# OOBD-Cup_v6.net
KiCad netlist of a schematic drawn in EAGLE
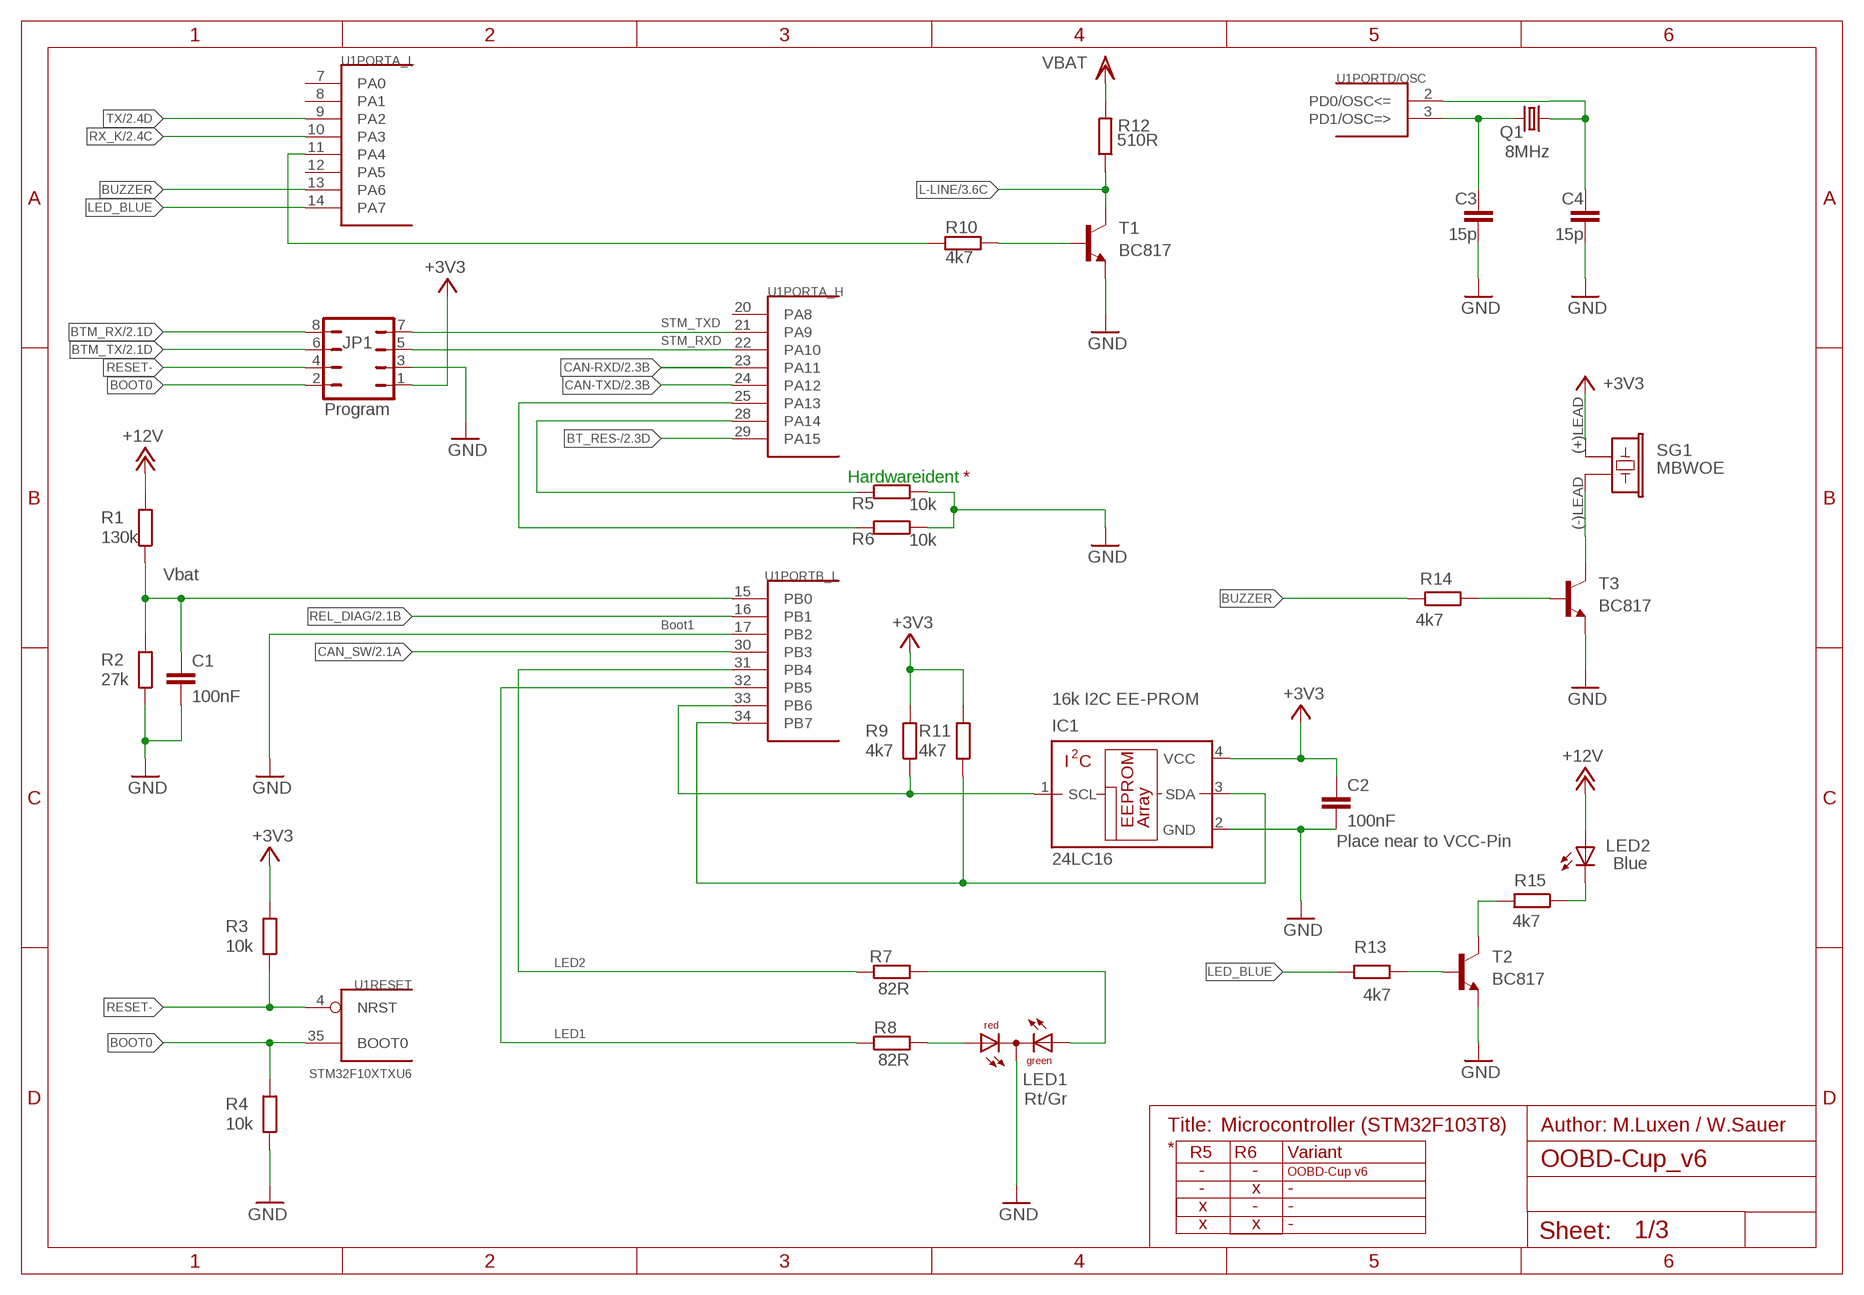
[diagram p0: schematic, sheet 1]
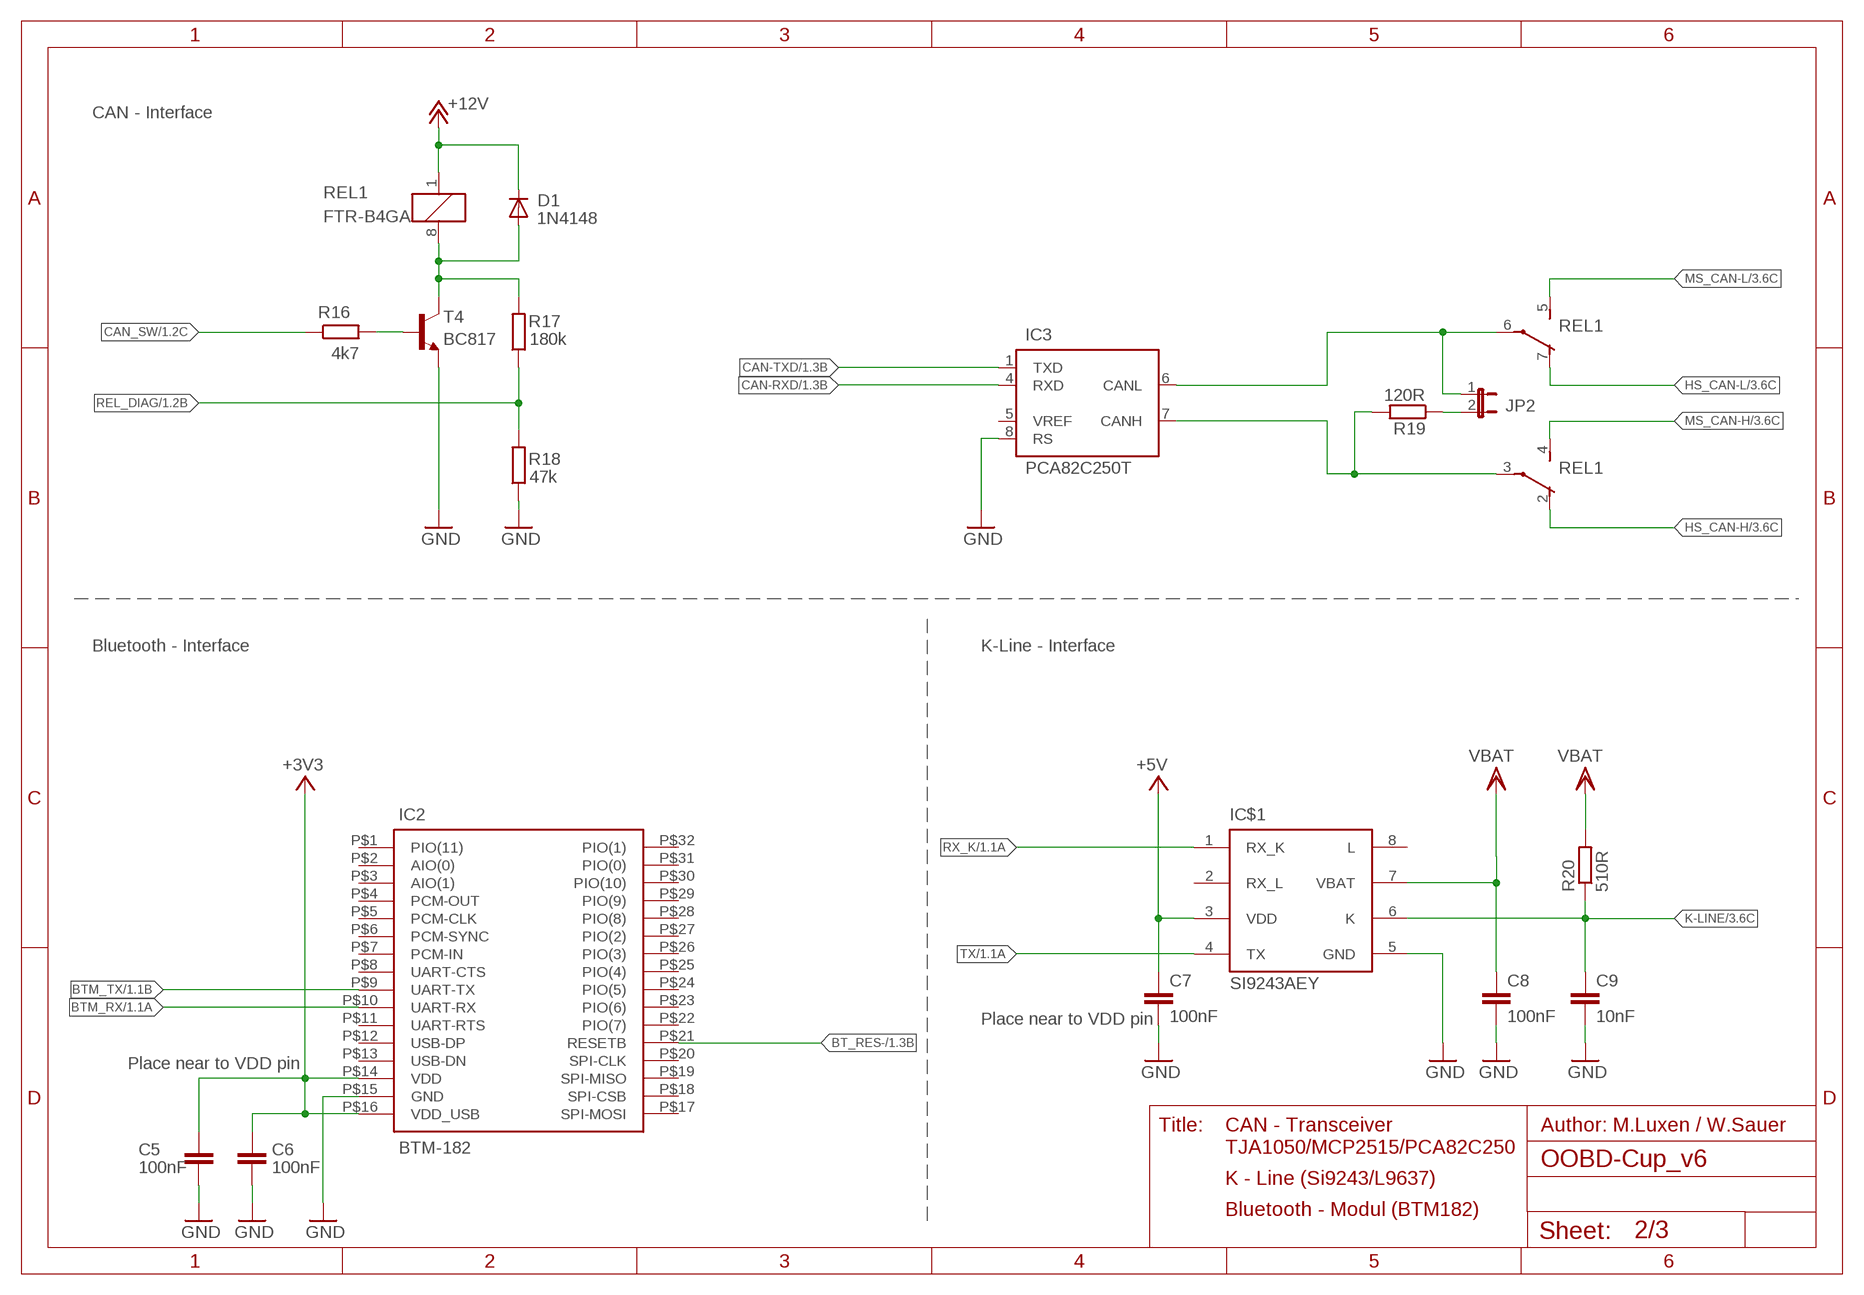
[diagram p1: schematic, sheet 2]
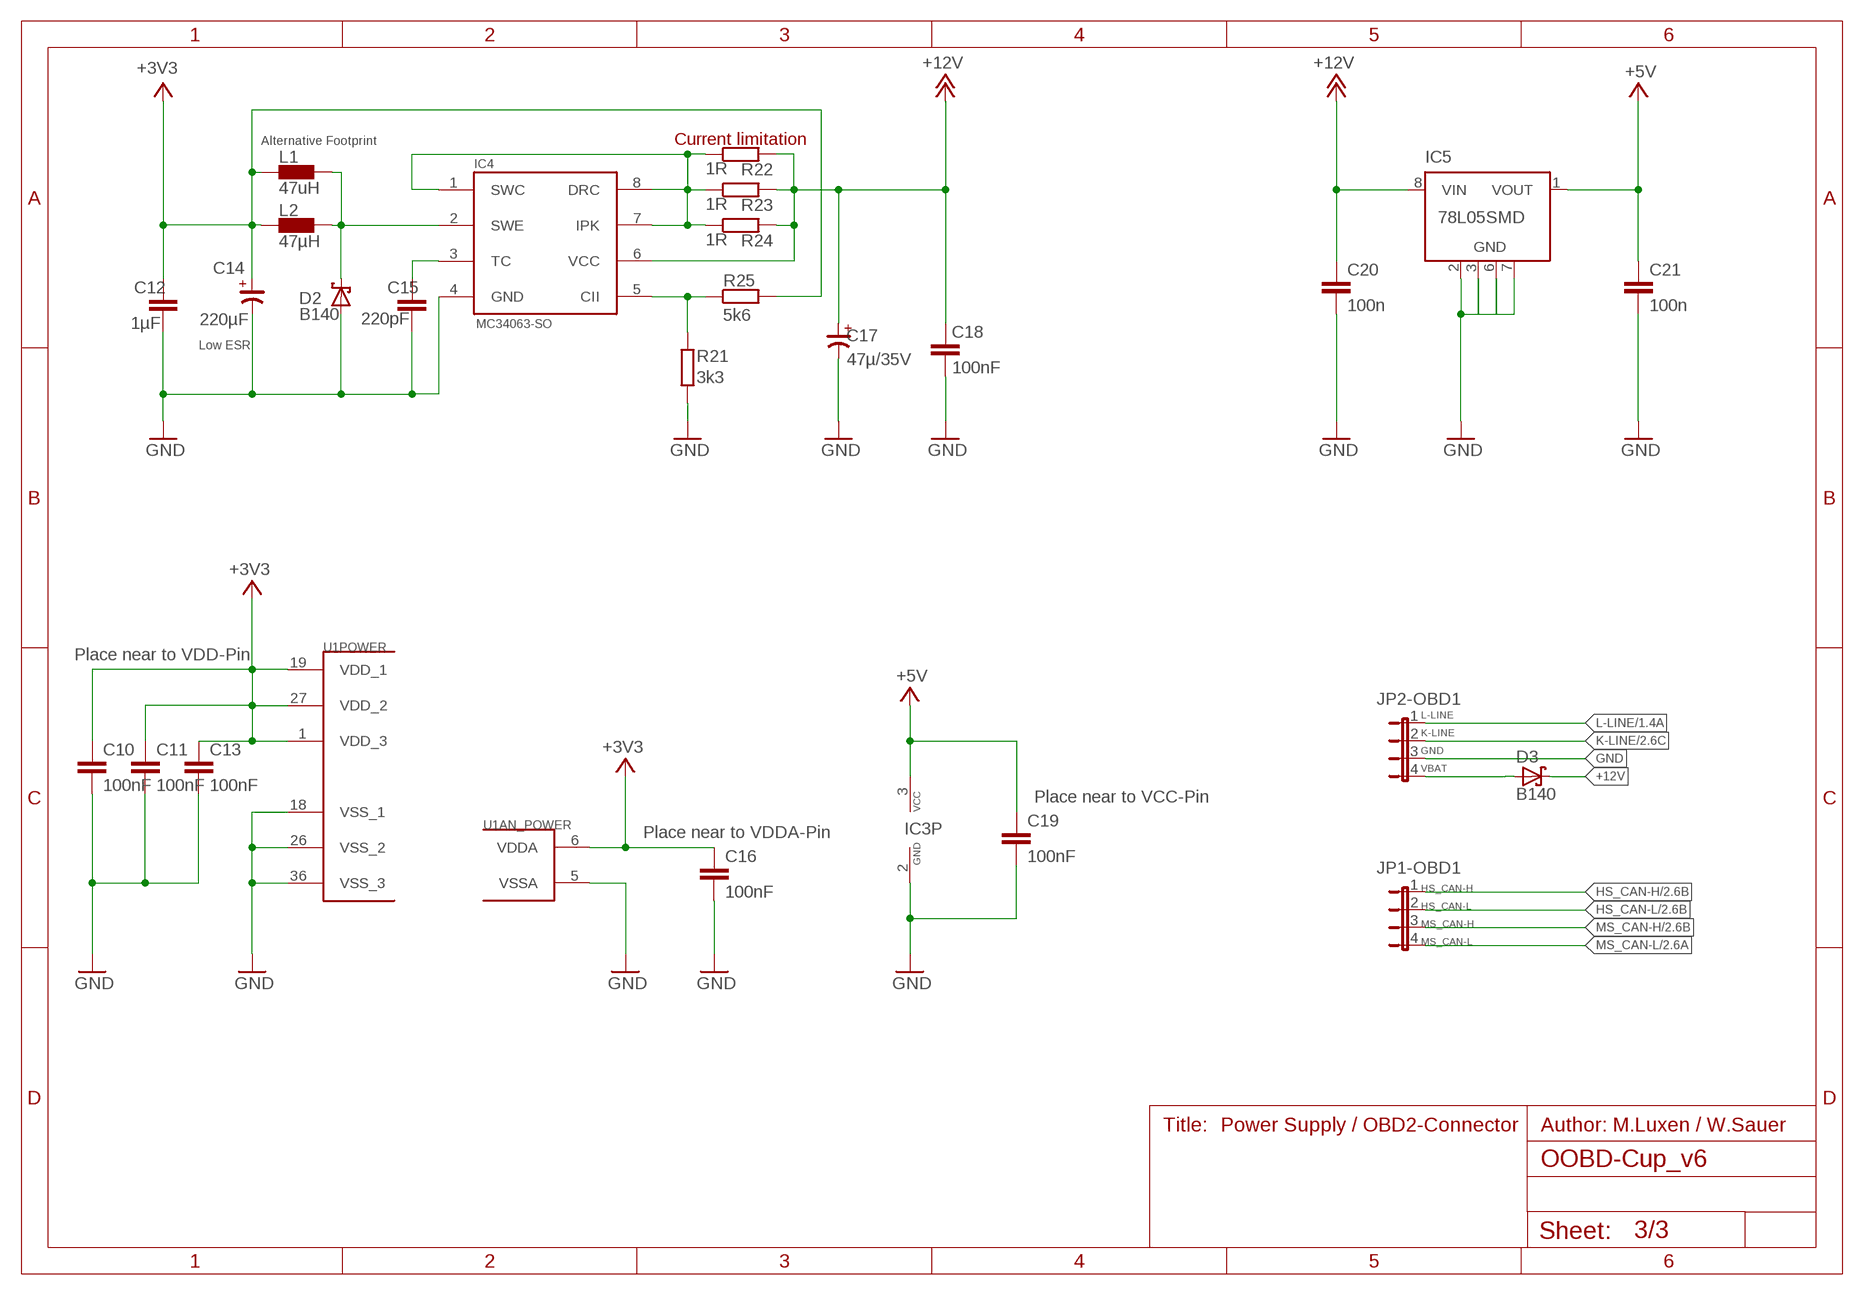
[diagram p2: schematic, sheet 3]

(export (version "E")
  (design (tool "Eeschema 10.0.6"))
  (components
    (comp (ref "C1")
      (value "100nF")
      (footprint "eagle-import:C0603")
      (libsource (lib "eagle-import") (part "resistor_C-EUC0603"))
    )
    (comp (ref "C2")
      (value "100nF")
      (footprint "eagle-import:C0603")
      (libsource (lib "eagle-import") (part "C-EUC0603"))
    )
    (comp (ref "C3")
      (value "15p")
      (footprint "eagle-import:C0603")
      (libsource (lib "eagle-import") (part "resistor_C-EUC0603"))
    )
    (comp (ref "C4")
      (value "15p")
      (footprint "eagle-import:C0603")
      (libsource (lib "eagle-import") (part "resistor_C-EUC0603"))
    )
    (comp (ref "IC1")
      (value "24LC16")
      (footprint "eagle-import:SOT23-5L")
      (fields (field (name "MF") "MICROCHIP") (field (name "MPN") "24LC00T-I/OT"))
      (libsource (lib "eagle-import") (part "2400OTLC"))
    )
    (comp (ref "JP1")
      (value "Program")
      (footprint "eagle-import:JP4Q")
      (libsource (lib "eagle-import") (part "JP4Q"))
    )
    (comp (ref "LED1")
      (value "Rt/Gr")
      (footprint "eagle-import:DUOLED2X5")
      (libsource (lib "eagle-import") (part "DUOLED2X5"))
    )
    (comp (ref "LED2")
      (value "Blue")
      (footprint "eagle-import:U57X32")
      (libsource (lib "eagle-import") (part "LEDSQR5.7X3.2"))
    )
    (comp (ref "Q1")
      (value "8MHz")
      (footprint "eagle-import:CTS406")
      (libsource (lib "eagle-import") (part "CRYSTALCTS406"))
    )
    (comp (ref "R1")
      (value "130k")
      (footprint "eagle-import:R0603")
      (libsource (lib "eagle-import") (part "resistor_R-EU_R0603"))
    )
    (comp (ref "R2")
      (value "27k")
      (footprint "eagle-import:R0603")
      (libsource (lib "eagle-import") (part "resistor_R-EU_R0603"))
    )
    (comp (ref "R3")
      (value "10k")
      (footprint "eagle-import:R0603")
      (libsource (lib "eagle-import") (part "resistor_R-EU_R0603"))
    )
    (comp (ref "R4")
      (value "10k")
      (footprint "eagle-import:R0603")
      (libsource (lib "eagle-import") (part "resistor_R-EU_R0603"))
    )
    (comp (ref "R5")
      (value "10k")
      (footprint "eagle-import:R0603")
      (libsource (lib "eagle-import") (part "R-EU_R0603"))
    )
    (comp (ref "R6")
      (value "10k")
      (footprint "eagle-import:R0603")
      (libsource (lib "eagle-import") (part "R-EU_R0603"))
    )
    (comp (ref "R7")
      (value "82R")
      (footprint "eagle-import:R0603")
      (libsource (lib "eagle-import") (part "R-EU_R0603"))
    )
    (comp (ref "R8")
      (value "82R")
      (footprint "eagle-import:R0603")
      (libsource (lib "eagle-import") (part "R-EU_R0603"))
    )
    (comp (ref "R9")
      (value "4k7")
      (footprint "eagle-import:R0603")
      (libsource (lib "eagle-import") (part "resistor_R-EU_R0603"))
    )
    (comp (ref "R10")
      (value "4k7")
      (footprint "eagle-import:R0603")
      (libsource (lib "eagle-import") (part "R-EU_R0603"))
    )
    (comp (ref "R11")
      (value "4k7")
      (footprint "eagle-import:R0603")
      (libsource (lib "eagle-import") (part "resistor_R-EU_R0603"))
    )
    (comp (ref "R12")
      (value "510R")
      (footprint "eagle-import:R0603")
      (libsource (lib "eagle-import") (part "R-EU_R0603"))
    )
    (comp (ref "R13")
      (value "4k7")
      (footprint "eagle-import:R0603")
      (libsource (lib "eagle-import") (part "R-EU_R0603"))
    )
    (comp (ref "R14")
      (value "4k7")
      (footprint "eagle-import:R0603")
      (libsource (lib "eagle-import") (part "R-EU_R0603"))
    )
    (comp (ref "R15")
      (value "4k7")
      (footprint "eagle-import:R0603")
      (libsource (lib "eagle-import") (part "R-EU_R0603"))
    )
    (comp (ref "SG1")
      (value "MBWOE")
      (footprint "eagle-import:BME0603SA")
      (fields (field (name "MF") "Grewus"))
      (libsource (lib "eagle-import") (part "MBWOE"))
    )
    (comp (ref "T1")
      (value "BC817")
      (footprint "eagle-import:SOT23")
      (libsource (lib "eagle-import") (part "BC847"))
    )
    (comp (ref "T2")
      (value "BC817")
      (footprint "eagle-import:SOT23")
      (libsource (lib "eagle-import") (part "BC847"))
    )
    (comp (ref "T3")
      (value "BC817")
      (footprint "eagle-import:SOT23")
      (libsource (lib "eagle-import") (part "BC847"))
    )
    (comp (ref "U1")
      (value "STM32F10XTXU6")
      (footprint "eagle-import:VFQFPN36")
      (libsource (lib "eagle-import") (part "STM32F10XTXU6"))
    )
    (comp (ref "C10")
      (value "100nF")
      (footprint "eagle-import:C0603")
      (libsource (lib "eagle-import") (part "resistor_C-EUC0603"))
    )
    (comp (ref "C11")
      (value "100nF")
      (footprint "eagle-import:C0603")
      (libsource (lib "eagle-import") (part "resistor_C-EUC0603"))
    )
    (comp (ref "C12")
      (value "1µF")
      (footprint "eagle-import:C0603K")
      (libsource (lib "eagle-import") (part "C-EUC0603K"))
    )
    (comp (ref "C13")
      (value "100nF")
      (footprint "eagle-import:C0603")
      (libsource (lib "eagle-import") (part "resistor_C-EUC0603"))
    )
    (comp (ref "C14")
      (value "220µF")
      (footprint "eagle-import:C6032-TE-C")
      (libsource (lib "eagle-import") (part "CP_6032-TE-C"))
    )
    (comp (ref "C15")
      (value "220pF")
      (footprint "eagle-import:C0603K")
      (libsource (lib "eagle-import") (part "C-EUC0603K"))
    )
    (comp (ref "C16")
      (value "100nF")
      (footprint "eagle-import:C0603")
      (libsource (lib "eagle-import") (part "resistor_C-EUC0603"))
    )
    (comp (ref "C17")
      (value "47µ/35V")
      (footprint "eagle-import:SV-D")
      (libsource (lib "eagle-import") (part "CP-SV-D"))
    )
    (comp (ref "C18")
      (value "100nF")
      (footprint "eagle-import:C0603K")
      (libsource (lib "eagle-import") (part "C-EUC0603K"))
    )
    (comp (ref "C19")
      (value "100nF")
      (footprint "eagle-import:C0603")
      (libsource (lib "eagle-import") (part "resistor_C-EUC0603"))
    )
    (comp (ref "C20")
      (value "100n")
      (footprint "eagle-import:C0603")
      (libsource (lib "eagle-import") (part "resistor_C-EUC0603"))
    )
    (comp (ref "C21")
      (value "100n")
      (footprint "eagle-import:C0603")
      (libsource (lib "eagle-import") (part "resistor_C-EUC0603"))
    )
    (comp (ref "D2")
      (value "B140")
      (footprint "eagle-import:SMB")
      (libsource (lib "eagle-import") (part "SCHOTTKY-DIODESMD"))
    )
    (comp (ref "D3")
      (value "B140")
      (footprint "eagle-import:SMB")
      (libsource (lib "eagle-import") (part "SCHOTTKY-DIODESMD"))
    )
    (comp (ref "IC3")
      (value "PCA82C250T")
      (footprint "eagle-import:SO08")
      (libsource (lib "eagle-import") (part "PCA82C250T"))
    )
    (comp (ref "IC4")
      (value "MC34063-SO")
      (footprint "eagle-import:SO8")
      (libsource (lib "eagle-import") (part "MC34063-SO"))
    )
    (comp (ref "IC5")
      (value "78L05SMD")
      (footprint "eagle-import:SO08")
      (libsource (lib "eagle-import") (part "78LSMD05"))
    )
    (comp (ref "JP1-OBD1")
      (value "JP4E")
      (footprint "eagle-import:JP4")
      (libsource (lib "eagle-import") (part "JP4E"))
    )
    (comp (ref "JP2-OBD1")
      (value "JP4E")
      (footprint "eagle-import:JP4")
      (libsource (lib "eagle-import") (part "JP4E"))
    )
    (comp (ref "L1")
      (value "47uH")
      (footprint "eagle-import:PIS2408")
      (libsource (lib "eagle-import") (part "PIS2408"))
    )
    (comp (ref "L2")
      (value "47µH")
      (footprint "eagle-import:07HCP-XXXX-50")
      (libsource (lib "eagle-import") (part "07HCP-XXXX-50"))
    )
    (comp (ref "R21")
      (value "3k3")
      (footprint "eagle-import:R0603")
      (libsource (lib "eagle-import") (part "R-EU_R0603"))
    )
    (comp (ref "R22")
      (value "1R")
      (footprint "eagle-import:R0805")
      (libsource (lib "eagle-import") (part "R-EU_R0805"))
    )
    (comp (ref "R23")
      (value "1R")
      (footprint "eagle-import:R0805")
      (libsource (lib "eagle-import") (part "R-EU_R0805"))
    )
    (comp (ref "R24")
      (value "1R")
      (footprint "eagle-import:R0805")
      (libsource (lib "eagle-import") (part "R-EU_R0805"))
    )
    (comp (ref "R25")
      (value "5k6")
      (footprint "eagle-import:R0603")
      (libsource (lib "eagle-import") (part "R-EU_R0603"))
    )
    (comp (ref "C5")
      (value "100nF")
      (footprint "eagle-import:C0603")
      (libsource (lib "eagle-import") (part "C-EUC0603"))
    )
    (comp (ref "C6")
      (value "100nF")
      (footprint "eagle-import:C0603")
      (libsource (lib "eagle-import") (part "C-EUC0603"))
    )
    (comp (ref "C7")
      (value "100nF")
      (footprint "eagle-import:C0603")
      (libsource (lib "eagle-import") (part "resistor_C-EUC0603"))
    )
    (comp (ref "C8")
      (value "100nF")
      (footprint "eagle-import:C0603")
      (libsource (lib "eagle-import") (part "resistor_C-EUC0603"))
    )
    (comp (ref "C9")
      (value "10nF")
      (footprint "eagle-import:C0603")
      (libsource (lib "eagle-import") (part "resistor_C-EUC0603"))
    )
    (comp (ref "D1")
      (value "1N4148")
      (footprint "eagle-import:MINIMELF")
      (libsource (lib "eagle-import") (part "DIODE-MINIMELF"))
    )
    (comp (ref "IC$1")
      (value "SI9243AEY")
      (footprint "eagle-import:SO08")
      (libsource (lib "eagle-import") (part "SI9243AEY"))
    )
    (comp (ref "IC2")
      (value "BTM-182")
      (footprint "eagle-import:BTM-182")
      (libsource (lib "eagle-import") (part "BTM-182"))
    )
    (comp (ref "JP2")
      (value "JP1E")
      (footprint "eagle-import:JP1")
      (libsource (lib "eagle-import") (part "JP1E"))
    )
    (comp (ref "R16")
      (value "4k7")
      (footprint "eagle-import:R0603")
      (libsource (lib "eagle-import") (part "R-EU_R0603"))
    )
    (comp (ref "R17")
      (value "180k")
      (footprint "eagle-import:R0603")
      (libsource (lib "eagle-import") (part "R-EU_R0603"))
    )
    (comp (ref "R18")
      (value "47k")
      (footprint "eagle-import:R0603")
      (libsource (lib "eagle-import") (part "R-EU_R0603"))
    )
    (comp (ref "R19")
      (value "120R")
      (footprint "eagle-import:R0603")
      (libsource (lib "eagle-import") (part "resistor_R-EU_R0603"))
    )
    (comp (ref "R20")
      (value "510R")
      (footprint "eagle-import:R0603")
      (libsource (lib "eagle-import") (part "resistor_R-EU_R0603"))
    )
    (comp (ref "REL1")
      (value "FTR-B4GA")
      (footprint "eagle-import:FTR-B4GA")
      (fields (field (name "MPN") "FTR-B4GAxxxZ"))
      (libsource (lib "eagle-import") (part "FTR-B4GA"))
    )
    (comp (ref "T4")
      (value "BC817")
      (footprint "eagle-import:SOT23")
      (libsource (lib "eagle-import") (part "BC847"))
    )
  )
  (nets
    (net (code "1") (name "+3V3") (class "Default")
      (node (ref "C10") (pin "1") (pinfunction "1_1") (pintype "passive"))
      (node (ref "C11") (pin "1") (pinfunction "1_1") (pintype "passive"))
      (node (ref "C12") (pin "1") (pinfunction "1_1") (pintype "passive"))
      (node (ref "C13") (pin "1") (pinfunction "1_1") (pintype "passive"))
      (node (ref "C14") (pin "+") (pinfunction "+_+") (pintype "passive"))
      (node (ref "C16") (pin "1") (pinfunction "1_1") (pintype "passive"))
      (node (ref "C2") (pin "1") (pinfunction "1_1") (pintype "passive"))
      (node (ref "C5") (pin "1") (pinfunction "1_1") (pintype "passive"))
      (node (ref "C6") (pin "1") (pinfunction "1_1") (pintype "passive"))
      (node (ref "IC1") (pin "4") (pinfunction "VCC_4") (pintype "power_in"))
      (node (ref "IC2") (pin "P$14") (pinfunction "VDD_P$14") (pintype "power_in"))
      (node (ref "IC2") (pin "P$16") (pinfunction "VDD_USB_P$16") (pintype "power_in"))
      (node (ref "JP1") (pin "1") (pinfunction "1_1") (pintype "passive"))
      (node (ref "L1") (pin "P$1") (pinfunction "P$1_P$1") (pintype "bidirectional"))
      (node (ref "L2") (pin "1") (pinfunction "P$1_1") (pintype "bidirectional"))
      (node (ref "R11") (pin "2") (pinfunction "2_2") (pintype "passive"))
      (node (ref "R25") (pin "2") (pinfunction "2_2") (pintype "passive"))
      (node (ref "R3") (pin "2") (pinfunction "2_2") (pintype "passive"))
      (node (ref "R9") (pin "2") (pinfunction "2_2") (pintype "passive"))
      (node (ref "SG1") (pin "(+)LEAD") (pinfunction "1_(+)LEAD") (pintype "passive"))
      (node (ref "U1") (pin "1") (pinfunction "VDD_3_1") (pintype "power_in"))
      (node (ref "U1") (pin "19") (pinfunction "VDD_1_19") (pintype "power_in"))
      (node (ref "U1") (pin "27") (pinfunction "VDD_2_27") (pintype "power_in"))
      (node (ref "U1") (pin "6") (pinfunction "VDDA_6") (pintype "power_in"))
    )
    (net (code "2") (name "+5V") (class "Default")
      (node (ref "C19") (pin "1") (pinfunction "1_1") (pintype "passive"))
      (node (ref "C21") (pin "1") (pinfunction "1_1") (pintype "passive"))
      (node (ref "C7") (pin "1") (pinfunction "1_1") (pintype "passive"))
      (node (ref "IC$1") (pin "3") (pinfunction "VDD_3") (pintype "bidirectional"))
      (node (ref "IC3") (pin "3") (pinfunction "VCC_3") (pintype "power_in"))
      (node (ref "IC5") (pin "1") (pinfunction "VOUT_1") (pintype "output"))
    )
    (net (code "3") (name "+12V") (class "Default")
      (node (ref "C17") (pin "+") (pinfunction "+_+") (pintype "passive"))
      (node (ref "C18") (pin "1") (pinfunction "1_1") (pintype "passive"))
      (node (ref "C20") (pin "1") (pinfunction "1_1") (pintype "passive"))
      (node (ref "D1") (pin "C") (pinfunction "C_C") (pintype "passive"))
      (node (ref "D3") (pin "C") (pinfunction "C_C") (pintype "passive"))
      (node (ref "IC4") (pin "6") (pinfunction "VCC_6") (pintype "bidirectional"))
      (node (ref "IC5") (pin "8") (pinfunction "VIN_8") (pintype "passive"))
      (node (ref "LED2") (pin "A") (pinfunction "A_A") (pintype "passive"))
      (node (ref "R1") (pin "2") (pinfunction "2_2") (pintype "passive"))
      (node (ref "R22") (pin "2") (pinfunction "2_2") (pintype "passive"))
      (node (ref "R23") (pin "2") (pinfunction "2_2") (pintype "passive"))
      (node (ref "R24") (pin "2") (pinfunction "2_2") (pintype "passive"))
      (node (ref "REL1") (pin "1") (pinfunction "1_1") (pintype "passive"))
    )
    (net (code "4") (name "BOOT0") (class "Default")
      (node (ref "JP1") (pin "2") (pinfunction "2_2") (pintype "passive"))
      (node (ref "R4") (pin "2") (pinfunction "2_2") (pintype "passive"))
      (node (ref "U1") (pin "35") (pinfunction "BOOT0_35") (pintype "input"))
    )
    (net (code "5") (name "BTM_RX") (class "Default")
      (node (ref "IC2") (pin "P$10") (pinfunction "UART-RX_P$10") (pintype "input"))
      (node (ref "JP1") (pin "8") (pinfunction "8_8") (pintype "passive"))
    )
    (net (code "6") (name "BTM_TX") (class "Default")
      (node (ref "IC2") (pin "P$9") (pinfunction "UART-TX_P$9") (pintype "output"))
      (node (ref "JP1") (pin "6") (pinfunction "6_6") (pintype "passive"))
    )
    (net (code "7") (name "BT_RES-") (class "Default")
      (node (ref "IC2") (pin "P$21") (pinfunction "RESETB_P$21") (pintype "input"))
      (node (ref "U1") (pin "29") (pinfunction "PA15_29") (pintype "bidirectional"))
    )
    (net (code "8") (name "BUZZER") (class "Default")
      (node (ref "R14") (pin "1") (pinfunction "1_1") (pintype "passive"))
      (node (ref "U1") (pin "13") (pinfunction "PA6_13") (pintype "bidirectional"))
    )
    (net (code "9") (name "CAN-RXD") (class "Default")
      (node (ref "IC3") (pin "4") (pinfunction "RXD_4") (pintype "bidirectional"))
      (node (ref "U1") (pin "23") (pinfunction "PA11_23") (pintype "bidirectional"))
    )
    (net (code "10") (name "CAN-TXD") (class "Default")
      (node (ref "IC3") (pin "1") (pinfunction "TXD_1") (pintype "bidirectional"))
      (node (ref "U1") (pin "24") (pinfunction "PA12_24") (pintype "bidirectional"))
    )
    (net (code "11") (name "CAN_SW") (class "Default")
      (node (ref "R16") (pin "1") (pinfunction "1_1") (pintype "passive"))
      (node (ref "U1") (pin "30") (pinfunction "PB3_30") (pintype "bidirectional"))
    )
    (net (code "12") (name "GND") (class "Default")
      (node (ref "C1") (pin "2") (pinfunction "2_2") (pintype "passive"))
      (node (ref "C10") (pin "2") (pinfunction "2_2") (pintype "passive"))
      (node (ref "C11") (pin "2") (pinfunction "2_2") (pintype "passive"))
      (node (ref "C12") (pin "2") (pinfunction "2_2") (pintype "passive"))
      (node (ref "C13") (pin "2") (pinfunction "2_2") (pintype "passive"))
      (node (ref "C14") (pin "-") (pinfunction "-_-") (pintype "passive"))
      (node (ref "C15") (pin "2") (pinfunction "2_2") (pintype "passive"))
      (node (ref "C16") (pin "2") (pinfunction "2_2") (pintype "passive"))
      (node (ref "C17") (pin "-") (pinfunction "-_-") (pintype "passive"))
      (node (ref "C18") (pin "2") (pinfunction "2_2") (pintype "passive"))
      (node (ref "C19") (pin "2") (pinfunction "2_2") (pintype "passive"))
      (node (ref "C2") (pin "2") (pinfunction "2_2") (pintype "passive"))
      (node (ref "C20") (pin "2") (pinfunction "2_2") (pintype "passive"))
      (node (ref "C21") (pin "2") (pinfunction "2_2") (pintype "passive"))
      (node (ref "C3") (pin "1") (pinfunction "1_1") (pintype "passive"))
      (node (ref "C4") (pin "1") (pinfunction "1_1") (pintype "passive"))
      (node (ref "C5") (pin "2") (pinfunction "2_2") (pintype "passive"))
      (node (ref "C6") (pin "2") (pinfunction "2_2") (pintype "passive"))
      (node (ref "C7") (pin "2") (pinfunction "2_2") (pintype "passive"))
      (node (ref "C8") (pin "2") (pinfunction "2_2") (pintype "passive"))
      (node (ref "C9") (pin "2") (pinfunction "2_2") (pintype "passive"))
      (node (ref "D2") (pin "A") (pinfunction "A_A") (pintype "passive"))
      (node (ref "IC$1") (pin "5") (pinfunction "GND_5") (pintype "bidirectional"))
      (node (ref "IC1") (pin "2") (pinfunction "GND_2") (pintype "power_in"))
      (node (ref "IC2") (pin "P$15") (pinfunction "GND_P$15") (pintype "power_in"))
      (node (ref "IC3") (pin "2") (pinfunction "GND_2") (pintype "power_in"))
      (node (ref "IC3") (pin "8") (pinfunction "RS_8") (pintype "bidirectional"))
      (node (ref "IC4") (pin "4") (pinfunction "GND_4") (pintype "power_in"))
      (node (ref "IC5") (pin "2") (pinfunction "GND_2") (pintype "power_in"))
      (node (ref "IC5") (pin "3") (pinfunction "GND_3") (pintype "power_in"))
      (node (ref "IC5") (pin "6") (pinfunction "GND_6") (pintype "power_in"))
      (node (ref "IC5") (pin "7") (pinfunction "GND_7") (pintype "power_in"))
      (node (ref "JP1") (pin "3") (pinfunction "3_3") (pintype "passive"))
      (node (ref "JP2-OBD1") (pin "3") (pinfunction "3_3") (pintype "passive"))
      (node (ref "LED1") (pin "K") (pinfunction "C_K") (pintype "passive"))
      (node (ref "R18") (pin "1") (pinfunction "1_1") (pintype "passive"))
      (node (ref "R2") (pin "1") (pinfunction "1_1") (pintype "passive"))
      (node (ref "R21") (pin "2") (pinfunction "2_2") (pintype "passive"))
      (node (ref "R4") (pin "1") (pinfunction "1_1") (pintype "passive"))
      (node (ref "R5") (pin "2") (pinfunction "2_2") (pintype "passive"))
      (node (ref "R6") (pin "2") (pinfunction "2_2") (pintype "passive"))
      (node (ref "T1") (pin "2") (pinfunction "E_2") (pintype "passive"))
      (node (ref "T2") (pin "2") (pinfunction "E_2") (pintype "passive"))
      (node (ref "T3") (pin "2") (pinfunction "E_2") (pintype "passive"))
      (node (ref "T4") (pin "2") (pinfunction "E_2") (pintype "passive"))
      (node (ref "U1") (pin "17") (pinfunction "PB2_17") (pintype "bidirectional"))
      (node (ref "U1") (pin "18") (pinfunction "VSS_1_18") (pintype "power_in"))
      (node (ref "U1") (pin "26") (pinfunction "VSS_2_26") (pintype "power_in"))
      (node (ref "U1") (pin "36") (pinfunction "VSS_3_36") (pintype "power_in"))
      (node (ref "U1") (pin "5") (pinfunction "VSSA_5") (pintype "power_in"))
    )
    (net (code "13") (name "HS_CAN-H") (class "Default")
      (node (ref "JP1-OBD1") (pin "1") (pinfunction "1_1") (pintype "passive"))
      (node (ref "REL1") (pin "2") (pinfunction "O_2") (pintype "passive"))
    )
    (net (code "14") (name "HS_CAN-L") (class "Default")
      (node (ref "JP1-OBD1") (pin "2") (pinfunction "2_2") (pintype "passive"))
      (node (ref "REL1") (pin "7") (pinfunction "O_7") (pintype "passive"))
    )
    (net (code "15") (name "K-LINE") (class "Default")
      (node (ref "C9") (pin "1") (pinfunction "1_1") (pintype "passive"))
      (node (ref "IC$1") (pin "6") (pinfunction "K_6") (pintype "bidirectional"))
      (node (ref "JP2-OBD1") (pin "2") (pinfunction "2_2") (pintype "passive"))
      (node (ref "R20") (pin "1") (pinfunction "1_1") (pintype "passive"))
    )
    (net (code "16") (name "L-LINE") (class "Default")
      (node (ref "JP2-OBD1") (pin "1") (pinfunction "1_1") (pintype "passive"))
      (node (ref "R12") (pin "1") (pinfunction "1_1") (pintype "passive"))
      (node (ref "T1") (pin "3") (pinfunction "C_3") (pintype "passive"))
    )
    (net (code "17") (name "LED1") (class "Default")
      (node (ref "R8") (pin "1") (pinfunction "1_1") (pintype "passive"))
      (node (ref "U1") (pin "32") (pinfunction "PB5_32") (pintype "bidirectional"))
    )
    (net (code "18") (name "LED2") (class "Default")
      (node (ref "R7") (pin "1") (pinfunction "1_1") (pintype "passive"))
      (node (ref "U1") (pin "31") (pinfunction "PB4_31") (pintype "bidirectional"))
    )
    (net (code "19") (name "LED_BLUE") (class "Default")
      (node (ref "R13") (pin "1") (pinfunction "1_1") (pintype "passive"))
      (node (ref "U1") (pin "14") (pinfunction "PA7_14") (pintype "bidirectional"))
    )
    (net (code "20") (name "MS_CAN-H") (class "Default")
      (node (ref "JP1-OBD1") (pin "3") (pinfunction "3_3") (pintype "passive"))
      (node (ref "REL1") (pin "4") (pinfunction "S_4") (pintype "passive"))
    )
    (net (code "21") (name "MS_CAN-L") (class "Default")
      (node (ref "JP1-OBD1") (pin "4") (pinfunction "4_4") (pintype "passive"))
      (node (ref "REL1") (pin "5") (pinfunction "S_5") (pintype "passive"))
    )
    (net (code "22") (name "Net-(IC1-SCL)") (class "Default")
      (node (ref "IC1") (pin "1") (pinfunction "SCL_1") (pintype "input"))
      (node (ref "R9") (pin "1") (pinfunction "1_1") (pintype "passive"))
      (node (ref "U1") (pin "33") (pinfunction "PB6_33") (pintype "bidirectional"))
    )
    (net (code "23") (name "Net-(IC1-SDA)") (class "Default")
      (node (ref "IC1") (pin "3") (pinfunction "SDA_3") (pintype "bidirectional"))
      (node (ref "R11") (pin "1") (pinfunction "1_1") (pintype "passive"))
      (node (ref "U1") (pin "34") (pinfunction "PB7_34") (pintype "bidirectional"))
    )
    (net (code "24") (name "Net-(IC3A-CANH)") (class "Default")
      (node (ref "IC3") (pin "7") (pinfunction "CANH_7") (pintype "bidirectional"))
      (node (ref "R19") (pin "2") (pinfunction "2_2") (pintype "passive"))
      (node (ref "REL1") (pin "3") (pinfunction "P_3") (pintype "passive"))
    )
    (net (code "25") (name "Net-(IC3A-CANL)") (class "Default")
      (node (ref "IC3") (pin "6") (pinfunction "CANL_6") (pintype "bidirectional"))
      (node (ref "JP2") (pin "1") (pinfunction "1_1") (pintype "passive"))
      (node (ref "REL1") (pin "6") (pinfunction "P_6") (pintype "passive"))
    )
    (net (code "26") (name "Net-(IC4-CII)") (class "Default")
      (node (ref "IC4") (pin "5") (pinfunction "CII_5") (pintype "bidirectional"))
      (node (ref "R21") (pin "1") (pinfunction "1_1") (pintype "passive"))
      (node (ref "R25") (pin "1") (pinfunction "1_1") (pintype "passive"))
    )
    (net (code "27") (name "Net-(IC4-DRC)") (class "Default")
      (node (ref "IC4") (pin "1") (pinfunction "SWC_1") (pintype "bidirectional"))
      (node (ref "IC4") (pin "7") (pinfunction "IPK_7") (pintype "bidirectional"))
      (node (ref "IC4") (pin "8") (pinfunction "DRC_8") (pintype "bidirectional"))
      (node (ref "R22") (pin "1") (pinfunction "1_1") (pintype "passive"))
      (node (ref "R23") (pin "1") (pinfunction "1_1") (pintype "passive"))
      (node (ref "R24") (pin "1") (pinfunction "1_1") (pintype "passive"))
    )
    (net (code "28") (name "Net-(IC4-SWE)") (class "Default")
      (node (ref "D2") (pin "C") (pinfunction "C_C") (pintype "passive"))
      (node (ref "IC4") (pin "2") (pinfunction "SWE_2") (pintype "bidirectional"))
      (node (ref "L1") (pin "P$2") (pinfunction "P$2_P$2") (pintype "bidirectional"))
      (node (ref "L2") (pin "2") (pinfunction "P$2_2") (pintype "bidirectional"))
    )
    (net (code "29") (name "Net-(IC4-TC)") (class "Default")
      (node (ref "C15") (pin "1") (pinfunction "1_1") (pintype "passive"))
      (node (ref "IC4") (pin "3") (pinfunction "TC_3") (pintype "bidirectional"))
    )
    (net (code "30") (name "Net-(JP2-Pad2)") (class "Default")
      (node (ref "JP2") (pin "2") (pinfunction "2_2") (pintype "passive"))
      (node (ref "R19") (pin "1") (pinfunction "1_1") (pintype "passive"))
    )
    (net (code "31") (name "Net-(LED1-PadAG)") (class "Default")
      (node (ref "LED1") (pin "AG") (pinfunction "AG_AG") (pintype "passive"))
      (node (ref "R7") (pin "2") (pinfunction "2_2") (pintype "passive"))
    )
    (net (code "32") (name "Net-(LED1-PadAR)") (class "Default")
      (node (ref "LED1") (pin "AR") (pinfunction "AR_AR") (pintype "passive"))
      (node (ref "R8") (pin "2") (pinfunction "2_2") (pintype "passive"))
    )
    (net (code "33") (name "Net-(LED2-C)") (class "Default")
      (node (ref "LED2") (pin "K") (pinfunction "C_K") (pintype "passive"))
      (node (ref "R15") (pin "1") (pinfunction "1_1") (pintype "passive"))
    )
    (net (code "34") (name "Net-(Q1-2)") (class "Default")
      (node (ref "C3") (pin "2") (pinfunction "2_2") (pintype "passive"))
      (node (ref "Q1") (pin "3") (pinfunction "2_3") (pintype "passive"))
      (node (ref "U1") (pin "3") (pinfunction "PD1/OSC=>_3") (pintype "bidirectional"))
    )
    (net (code "35") (name "Net-(REL1A-2)") (class "Default")
      (node (ref "D1") (pin "A") (pinfunction "A_A") (pintype "passive"))
      (node (ref "R17") (pin "2") (pinfunction "2_2") (pintype "passive"))
      (node (ref "REL1") (pin "8") (pinfunction "2_8") (pintype "passive"))
      (node (ref "T4") (pin "3") (pinfunction "C_3") (pintype "passive"))
    )
    (net (code "36") (name "Net-(SG1-2)") (class "Default")
      (node (ref "SG1") (pin "(-)LEAD") (pinfunction "2_(-)LEAD") (pintype "passive"))
      (node (ref "T3") (pin "3") (pinfunction "C_3") (pintype "passive"))
    )
    (net (code "37") (name "Net-(T1-B)") (class "Default")
      (node (ref "R10") (pin "2") (pinfunction "2_2") (pintype "passive"))
      (node (ref "T1") (pin "1") (pinfunction "B_1") (pintype "passive"))
    )
    (net (code "38") (name "Net-(T2-B)") (class "Default")
      (node (ref "R13") (pin "2") (pinfunction "2_2") (pintype "passive"))
      (node (ref "T2") (pin "1") (pinfunction "B_1") (pintype "passive"))
    )
    (net (code "39") (name "Net-(T2-C)") (class "Default")
      (node (ref "R15") (pin "2") (pinfunction "2_2") (pintype "passive"))
      (node (ref "T2") (pin "3") (pinfunction "C_3") (pintype "passive"))
    )
    (net (code "40") (name "Net-(T3-B)") (class "Default")
      (node (ref "R14") (pin "2") (pinfunction "2_2") (pintype "passive"))
      (node (ref "T3") (pin "1") (pinfunction "B_1") (pintype "passive"))
    )
    (net (code "41") (name "Net-(T4-B)") (class "Default")
      (node (ref "R16") (pin "2") (pinfunction "2_2") (pintype "passive"))
      (node (ref "T4") (pin "1") (pinfunction "B_1") (pintype "passive"))
    )
    (net (code "42") (name "Net-(U1B-PA13)") (class "Default")
      (node (ref "R6") (pin "1") (pinfunction "1_1") (pintype "passive"))
      (node (ref "U1") (pin "25") (pinfunction "PA13_25") (pintype "bidirectional"))
    )
    (net (code "43") (name "Net-(U1B-PA14)") (class "Default")
      (node (ref "R5") (pin "1") (pinfunction "1_1") (pintype "passive"))
      (node (ref "U1") (pin "28") (pinfunction "PA14_28") (pintype "bidirectional"))
    )
    (net (code "44") (name "Net-(U1C-PA4)") (class "Default")
      (node (ref "R10") (pin "1") (pinfunction "1_1") (pintype "passive"))
      (node (ref "U1") (pin "11") (pinfunction "PA4_11") (pintype "bidirectional"))
    )
    (net (code "45") (name "Net-(U1D-PB0)") (class "Default")
      (node (ref "C1") (pin "1") (pinfunction "1_1") (pintype "passive"))
      (node (ref "R1") (pin "1") (pinfunction "1_1") (pintype "passive"))
      (node (ref "R2") (pin "2") (pinfunction "2_2") (pintype "passive"))
      (node (ref "U1") (pin "15") (pinfunction "PB0_15") (pintype "bidirectional"))
    )
    (net (code "46") (name "Net-(U1E-PD0{slash}OSC<=)") (class "Default")
      (node (ref "C4") (pin "2") (pinfunction "2_2") (pintype "passive"))
      (node (ref "Q1") (pin "1") (pinfunction "1_1") (pintype "passive"))
      (node (ref "U1") (pin "2") (pinfunction "PD0/OSC<=_2") (pintype "bidirectional"))
    )
    (net (code "47") (name "REL_DIAG") (class "Default")
      (node (ref "R17") (pin "1") (pinfunction "1_1") (pintype "passive"))
      (node (ref "R18") (pin "2") (pinfunction "2_2") (pintype "passive"))
      (node (ref "U1") (pin "16") (pinfunction "PB1_16") (pintype "bidirectional"))
    )
    (net (code "48") (name "RESET-") (class "Default")
      (node (ref "JP1") (pin "4") (pinfunction "4_4") (pintype "passive"))
      (node (ref "R3") (pin "1") (pinfunction "1_1") (pintype "passive"))
      (node (ref "U1") (pin "4") (pinfunction "NRST_4") (pintype "input"))
    )
    (net (code "49") (name "RX_K") (class "Default")
      (node (ref "IC$1") (pin "1") (pinfunction "RX_K_1") (pintype "bidirectional"))
      (node (ref "U1") (pin "10") (pinfunction "PA3_10") (pintype "bidirectional"))
    )
    (net (code "50") (name "STM_RXD") (class "Default")
      (node (ref "JP1") (pin "5") (pinfunction "5_5") (pintype "passive"))
      (node (ref "U1") (pin "22") (pinfunction "PA10_22") (pintype "bidirectional"))
    )
    (net (code "51") (name "STM_TXD") (class "Default")
      (node (ref "JP1") (pin "7") (pinfunction "7_7") (pintype "passive"))
      (node (ref "U1") (pin "21") (pinfunction "PA9_21") (pintype "bidirectional"))
    )
    (net (code "52") (name "TX") (class "Default")
      (node (ref "IC$1") (pin "4") (pinfunction "TX_4") (pintype "bidirectional"))
      (node (ref "U1") (pin "9") (pinfunction "PA2_9") (pintype "bidirectional"))
    )
    (net (code "53") (name "VBAT") (class "Default")
      (node (ref "C8") (pin "1") (pinfunction "1_1") (pintype "passive"))
      (node (ref "D3") (pin "A") (pinfunction "A_A") (pintype "passive"))
      (node (ref "IC$1") (pin "7") (pinfunction "VBAT_7") (pintype "bidirectional"))
      (node (ref "JP2-OBD1") (pin "4") (pinfunction "4_4") (pintype "passive"))
      (node (ref "R12") (pin "2") (pinfunction "2_2") (pintype "passive"))
      (node (ref "R20") (pin "2") (pinfunction "2_2") (pintype "passive"))
    )
    (net (code "54") (name "unconnected-(IC$1-L-Pad8)") (class "Default")
      (node (ref "IC$1") (pin "8") (pinfunction "L_8") (pintype "bidirectional"))
    )
    (net (code "55") (name "unconnected-(IC$1-RX_L-Pad2)") (class "Default")
      (node (ref "IC$1") (pin "2") (pinfunction "RX_L_2") (pintype "bidirectional"))
    )
    (net (code "56") (name "unconnected-(IC2-AIO(0)-PadP$2)") (class "Default")
      (node (ref "IC2") (pin "P$2") (pinfunction "AIO(0)_P$2") (pintype "bidirectional"))
    )
    (net (code "57") (name "unconnected-(IC2-AIO(1)-PadP$3)") (class "Default")
      (node (ref "IC2") (pin "P$3") (pinfunction "AIO(1)_P$3") (pintype "bidirectional"))
    )
    (net (code "58") (name "unconnected-(IC2-PCM-CLK-PadP$5)") (class "Default")
      (node (ref "IC2") (pin "P$5") (pinfunction "PCM-CLK_P$5") (pintype "bidirectional"))
    )
    (net (code "59") (name "unconnected-(IC2-PCM-IN-PadP$7)") (class "Default")
      (node (ref "IC2") (pin "P$7") (pinfunction "PCM-IN_P$7") (pintype "input"))
    )
    (net (code "60") (name "unconnected-(IC2-PCM-OUT-PadP$4)") (class "Default")
      (node (ref "IC2") (pin "P$4") (pinfunction "PCM-OUT_P$4") (pintype "output"))
    )
    (net (code "61") (name "unconnected-(IC2-PCM-SYNC-PadP$6)") (class "Default")
      (node (ref "IC2") (pin "P$6") (pinfunction "PCM-SYNC_P$6") (pintype "bidirectional"))
    )
    (net (code "62") (name "unconnected-(IC2-PIO(0)-PadP$31)") (class "Default")
      (node (ref "IC2") (pin "P$31") (pinfunction "PIO(0)_P$31") (pintype "bidirectional"))
    )
    (net (code "63") (name "unconnected-(IC2-PIO(1)-PadP$32)") (class "Default")
      (node (ref "IC2") (pin "P$32") (pinfunction "PIO(1)_P$32") (pintype "bidirectional"))
    )
    (net (code "64") (name "unconnected-(IC2-PIO(2)-PadP$27)") (class "Default")
      (node (ref "IC2") (pin "P$27") (pinfunction "PIO(2)_P$27") (pintype "bidirectional"))
    )
    (net (code "65") (name "unconnected-(IC2-PIO(3)-PadP$26)") (class "Default")
      (node (ref "IC2") (pin "P$26") (pinfunction "PIO(3)_P$26") (pintype "bidirectional"))
    )
    (net (code "66") (name "unconnected-(IC2-PIO(4)-PadP$25)") (class "Default")
      (node (ref "IC2") (pin "P$25") (pinfunction "PIO(4)_P$25") (pintype "bidirectional"))
    )
    (net (code "67") (name "unconnected-(IC2-PIO(5)-PadP$24)") (class "Default")
      (node (ref "IC2") (pin "P$24") (pinfunction "PIO(5)_P$24") (pintype "bidirectional"))
    )
    (net (code "68") (name "unconnected-(IC2-PIO(6)-PadP$23)") (class "Default")
      (node (ref "IC2") (pin "P$23") (pinfunction "PIO(6)_P$23") (pintype "bidirectional"))
    )
    (net (code "69") (name "unconnected-(IC2-PIO(7)-PadP$22)") (class "Default")
      (node (ref "IC2") (pin "P$22") (pinfunction "PIO(7)_P$22") (pintype "bidirectional"))
    )
    (net (code "70") (name "unconnected-(IC2-PIO(8)-PadP$28)") (class "Default")
      (node (ref "IC2") (pin "P$28") (pinfunction "PIO(8)_P$28") (pintype "bidirectional"))
    )
    (net (code "71") (name "unconnected-(IC2-PIO(9)-PadP$29)") (class "Default")
      (node (ref "IC2") (pin "P$29") (pinfunction "PIO(9)_P$29") (pintype "bidirectional"))
    )
    (net (code "72") (name "unconnected-(IC2-PIO(10)-PadP$30)") (class "Default")
      (node (ref "IC2") (pin "P$30") (pinfunction "PIO(10)_P$30") (pintype "bidirectional"))
    )
    (net (code "73") (name "unconnected-(IC2-PIO(11)-PadP$1)") (class "Default")
      (node (ref "IC2") (pin "P$1") (pinfunction "PIO(11)_P$1") (pintype "bidirectional"))
    )
    (net (code "74") (name "unconnected-(IC2-SPI-CLK-PadP$20)") (class "Default")
      (node (ref "IC2") (pin "P$20") (pinfunction "SPI-CLK_P$20") (pintype "input"))
    )
    (net (code "75") (name "unconnected-(IC2-SPI-CSB-PadP$18)") (class "Default")
      (node (ref "IC2") (pin "P$18") (pinfunction "SPI-CSB_P$18") (pintype "input"))
    )
    (net (code "76") (name "unconnected-(IC2-SPI-MISO-PadP$19)") (class "Default")
      (node (ref "IC2") (pin "P$19") (pinfunction "SPI-MISO_P$19") (pintype "output"))
    )
    (net (code "77") (name "unconnected-(IC2-SPI-MOSI-PadP$17)") (class "Default")
      (node (ref "IC2") (pin "P$17") (pinfunction "SPI-MOSI_P$17") (pintype "input"))
    )
    (net (code "78") (name "unconnected-(IC2-UART-CTS-PadP$8)") (class "Default")
      (node (ref "IC2") (pin "P$8") (pinfunction "UART-CTS_P$8") (pintype "input"))
    )
    (net (code "79") (name "unconnected-(IC2-UART-RTS-PadP$11)") (class "Default")
      (node (ref "IC2") (pin "P$11") (pinfunction "UART-RTS_P$11") (pintype "output"))
    )
    (net (code "80") (name "unconnected-(IC2-USB-DN-PadP$13)") (class "Default")
      (node (ref "IC2") (pin "P$13") (pinfunction "USB-DN_P$13") (pintype "bidirectional"))
    )
    (net (code "81") (name "unconnected-(IC2-USB-DP-PadP$12)") (class "Default")
      (node (ref "IC2") (pin "P$12") (pinfunction "USB-DP_P$12") (pintype "bidirectional"))
    )
    (net (code "82") (name "unconnected-(IC3A-VREF-Pad5)") (class "Default")
      (node (ref "IC3") (pin "5") (pinfunction "VREF_5") (pintype "bidirectional"))
    )
    (net (code "83") (name "unconnected-(U1B-PA8-Pad20)") (class "Default")
      (node (ref "U1") (pin "20") (pinfunction "PA8_20") (pintype "bidirectional"))
    )
    (net (code "84") (name "unconnected-(U1C-PA0-Pad7)") (class "Default")
      (node (ref "U1") (pin "7") (pinfunction "PA0_7") (pintype "bidirectional"))
    )
    (net (code "85") (name "unconnected-(U1C-PA1-Pad8)") (class "Default")
      (node (ref "U1") (pin "8") (pinfunction "PA1_8") (pintype "bidirectional"))
    )
    (net (code "86") (name "unconnected-(U1C-PA5-Pad12)") (class "Default")
      (node (ref "U1") (pin "12") (pinfunction "PA5_12") (pintype "bidirectional"))
    )
  )
)
